# IR_SENSOR.net
KiCad netlist of a schematic drawn in Altium Designer
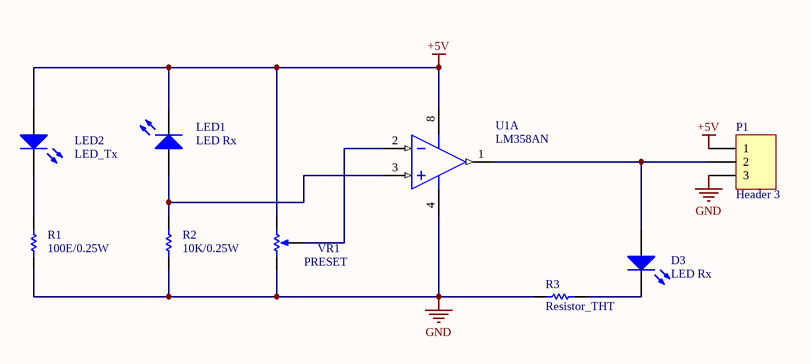
[diagram p0: IR_SENSOR.SchDoc]

(export (version "E")
  (design (tool "Eeschema 10.0.6"))
  (components
    (comp (ref "D3")
      (value "LED Rx")
      (footprint "LED-1")
      (description "Typical RED GaAs LED")
      (fields (field (name "PUBLISHER") "Altium Limited"))
      (libsource (lib "Miscellaneous Devices") (part "LED1"))
    )
    (comp (ref "LED1")
      (value "LED Rx")
      (footprint "LED-1")
      (description "Typical RED GaAs LED")
      (fields (field (name "PUBLISHER") "Altium Limited"))
      (libsource (lib "Miscellaneous Devices") (part "LED1"))
    )
    (comp (ref "LED2")
      (value "LED_Tx")
      (footprint "LED-1")
      (description "Typical RED GaAs LED")
      (fields (field (name "PUBLISHER") "Altium Limited"))
      (libsource (lib "Miscellaneous Devices") (part "LED1"))
    )
    (comp (ref "P1")
      (value "Header 3")
      (footprint "HDR1X3")
      (description "Header, 3-Pin")
      (fields (field (name "PUBLISHER") "Altium Limited"))
      (libsource (lib "Miscellaneous Connectors") (part "Header 3"))
    )
    (comp (ref "R1")
      (value "100E/0.25W")
      (footprint "AXIAL-0.3")
      (description "Resistor")
      (fields (field (name "Comment") "8-Jun-2000") (field (name "PUBLISHER") "Altium Limited"))
      (libsource (lib "Miscellaneous Devices") (part "Res1"))
    )
    (comp (ref "R2")
      (value "10K/0.25W")
      (footprint "AXIAL-0.3")
      (description "Resistor")
      (fields (field (name "Comment") "Res1") (field (name "PUBLISHER") "Altium Limited"))
      (libsource (lib "Miscellaneous Devices") (part "Res1"))
    )
    (comp (ref "R3")
      (value "Resistor_THT")
      (footprint "AXIAL-0.3")
      (description "Resistor")
      (fields (field (name "PUBLISHER") "Altium Limited"))
      (libsource (lib "Miscellaneous Devices") (part "Res1"))
    )
    (comp (ref "U1")
      (value "LM358AN")
      (footprint "N08E")
      (description "Low Power Dual Operational Amplifier")
      (fields
        (field (name "MANUFACTURER") "National Semiconductor")
        (field (name "DIGIKEYPARTNUMBER") "LM358ANNS-ND")
        (field (name "PUBLISHER") "Altium Limited")
      )
      (libsource (lib "NSC Amplifier") (part "LM358AN"))
    )
    (comp (ref "VR1")
      (value "VR1")
      (footprint "VR5")
      (description "Potentiometer")
      (fields (field (name "ALTIUM_VALUE") "PRESET") (field (name "PUBLISHER") "Altium Limited"))
      (libsource (lib "Miscellaneous Devices") (part "RPot"))
    )
  )
  (nets
    (net (code "1") (name "+5V") (class "Default")
      (node (ref "LED1") (pin "2") (pinfunction "K_2") (pintype "passive"))
      (node (ref "LED2") (pin "1") (pinfunction "A_1") (pintype "passive"))
      (node (ref "P1") (pin "1") (pinfunction "1_1") (pintype "passive"))
      (node (ref "U1") (pin "8") (pinfunction "V+_8") (pintype "power_in"))
      (node (ref "VR1") (pin "2") (pinfunction "BOT_2") (pintype "passive"))
    )
    (net (code "2") (name "GND") (class "Default")
      (node (ref "P1") (pin "3") (pinfunction "3_3") (pintype "passive"))
      (node (ref "R1") (pin "1") (pinfunction "1_1") (pintype "passive"))
      (node (ref "R2") (pin "1") (pinfunction "1_1") (pintype "passive"))
      (node (ref "R3") (pin "2") (pinfunction "2_2") (pintype "passive"))
      (node (ref "U1") (pin "4") (pinfunction "GND_4") (pintype "power_in"))
      (node (ref "VR1") (pin "1") (pinfunction "TOP_1") (pintype "passive"))
    )
    (net (code "3") (name "Net-(D3-A)") (class "Default")
      (node (ref "D3") (pin "1") (pinfunction "A_1") (pintype "passive"))
      (node (ref "P1") (pin "2") (pinfunction "2_2") (pintype "passive"))
      (node (ref "U1") (pin "1") (pinfunction "OUTA_1") (pintype "output"))
    )
    (net (code "4") (name "Net-(D3-K)") (class "Default")
      (node (ref "D3") (pin "2") (pinfunction "K_2") (pintype "passive"))
      (node (ref "R3") (pin "1") (pinfunction "1_1") (pintype "passive"))
    )
    (net (code "5") (name "Net-(LED1-A)") (class "Default")
      (node (ref "LED1") (pin "1") (pinfunction "A_1") (pintype "passive"))
      (node (ref "R2") (pin "2") (pinfunction "2_2") (pintype "passive"))
      (node (ref "U1") (pin "3") (pinfunction "INA+_3") (pintype "input"))
    )
    (net (code "6") (name "Net-(LED2-K)") (class "Default")
      (node (ref "LED2") (pin "2") (pinfunction "K_2") (pintype "passive"))
      (node (ref "R1") (pin "2") (pinfunction "2_2") (pintype "passive"))
    )
    (net (code "7") (name "Net-(U1A-INA-)") (class "Default")
      (node (ref "U1") (pin "2") (pinfunction "INA-_2") (pintype "input"))
      (node (ref "VR1") (pin "3") (pinfunction "TAP_3") (pintype "passive"))
    )
  )
)
